# Stepper_control.net
KiCad netlist of a schematic drawn in Altium Designer
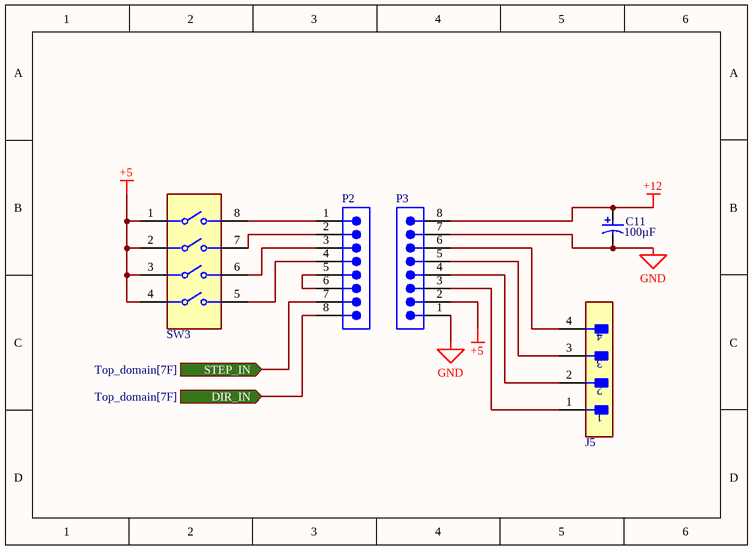
[diagram p0: Stepper_control.SchDoc]

(export (version "E")
  (design (tool "Eeschema 10.0.6"))
  (components
    (comp (ref "C11")
      (value "EEEFK1E101XP")
      (footprint "PNSC-FK-V-D8_V")
      (fields (field (name "CAPACITANCE") "100µF") (field (name "MANUFACTURER") "Panasonic"))
      (libsource (lib "Altium Content Vault") (part "CAP-P-2"))
    )
    (comp (ref "J5")
      (value "B4B-XH-A(LF)(SN)")
      (footprint "FP-B4B-XH-A_LF_SN-MFG")
      (description "CONN HEADER VERT 4POS 2.5MM")
      (libsource (lib "Altium Content Vault") (part "299a8cea1bdcbc3624fe62c390fa72c"))
    )
    (comp (ref "P2")
      (value "61300811121")
      (footprint "61300811121")
      (libsource (lib "Altium Content Vault") (part "Header_Male_1R_08P"))
    )
    (comp (ref "P3")
      (value "61300811121")
      (footprint "61300811121")
      (libsource (lib "Altium Content Vault") (part "Header_Male_1R_08P"))
    )
    (comp (ref "SW3")
      (value "1825360-3")
      (footprint "FP-1825360-3-MFG")
      (description "SWITCH SLIDE DIP SPST 100MA 24V")
      (libsource (lib "Altium Content Vault") (part "8a6f13ad003845d0737bd9d25158ffb"))
    )
  )
  (nets
    (net (code "1") (name "+5") (class "Default")
      (node (ref "P3") (pin "2") (pinfunction "2_2") (pintype "passive"))
      (node (ref "SW3") (pin "1") (pinfunction "1_1") (pintype "passive"))
      (node (ref "SW3") (pin "2") (pinfunction "2_2") (pintype "passive"))
      (node (ref "SW3") (pin "3") (pinfunction "3_3") (pintype "passive"))
      (node (ref "SW3") (pin "4") (pinfunction "4_4") (pintype "passive"))
    )
    (net (code "2") (name "+12") (class "Default")
      (node (ref "C11") (pin "1") (pinfunction "1_1") (pintype "passive"))
      (node (ref "P3") (pin "8") (pinfunction "8_8") (pintype "passive"))
    )
    (net (code "3") (name "/DIR_IN") (class "Default")
      (node (ref "P2") (pin "8") (pinfunction "8_8") (pintype "passive"))
    )
    (net (code "4") (name "/STEP_IN") (class "Default")
      (node (ref "P2") (pin "7") (pinfunction "7_7") (pintype "passive"))
    )
    (net (code "5") (name "GND") (class "Default")
      (node (ref "C11") (pin "2") (pinfunction "2_2") (pintype "passive"))
      (node (ref "P3") (pin "1") (pinfunction "1_1") (pintype "passive"))
      (node (ref "P3") (pin "7") (pinfunction "7_7") (pintype "passive"))
    )
    (net (code "6") (name "Net-(J5-Pad1)") (class "Default")
      (node (ref "J5") (pin "1") (pinfunction "1_1") (pintype "passive"))
      (node (ref "P3") (pin "3") (pinfunction "3_3") (pintype "passive"))
    )
    (net (code "7") (name "Net-(J5-Pad2)") (class "Default")
      (node (ref "J5") (pin "2") (pinfunction "2_2") (pintype "passive"))
      (node (ref "P3") (pin "4") (pinfunction "4_4") (pintype "passive"))
    )
    (net (code "8") (name "Net-(J5-Pad3)") (class "Default")
      (node (ref "J5") (pin "3") (pinfunction "3_3") (pintype "passive"))
      (node (ref "P3") (pin "5") (pinfunction "5_5") (pintype "passive"))
    )
    (net (code "9") (name "Net-(J5-Pad4)") (class "Default")
      (node (ref "J5") (pin "4") (pinfunction "4_4") (pintype "passive"))
      (node (ref "P3") (pin "6") (pinfunction "6_6") (pintype "passive"))
    )
    (net (code "10") (name "Net-(P2-Pad1)") (class "Default")
      (node (ref "P2") (pin "1") (pinfunction "1_1") (pintype "passive"))
      (node (ref "SW3") (pin "8") (pinfunction "8_8") (pintype "passive"))
    )
    (net (code "11") (name "Net-(P2-Pad2)") (class "Default")
      (node (ref "P2") (pin "2") (pinfunction "2_2") (pintype "passive"))
      (node (ref "SW3") (pin "7") (pinfunction "7_7") (pintype "passive"))
    )
    (net (code "12") (name "Net-(P2-Pad3)") (class "Default")
      (node (ref "P2") (pin "3") (pinfunction "3_3") (pintype "passive"))
      (node (ref "SW3") (pin "6") (pinfunction "6_6") (pintype "passive"))
    )
    (net (code "13") (name "Net-(P2-Pad4)") (class "Default")
      (node (ref "P2") (pin "4") (pinfunction "4_4") (pintype "passive"))
      (node (ref "SW3") (pin "5") (pinfunction "5_5") (pintype "passive"))
    )
    (net (code "14") (name "Net-(P2-Pad5)") (class "Default")
      (node (ref "P2") (pin "5") (pinfunction "5_5") (pintype "passive"))
      (node (ref "P2") (pin "6") (pinfunction "6_6") (pintype "passive"))
    )
  )
)
